# Arduino_Uno_Rev3.net
KiCad netlist of a schematic drawn in EAGLE
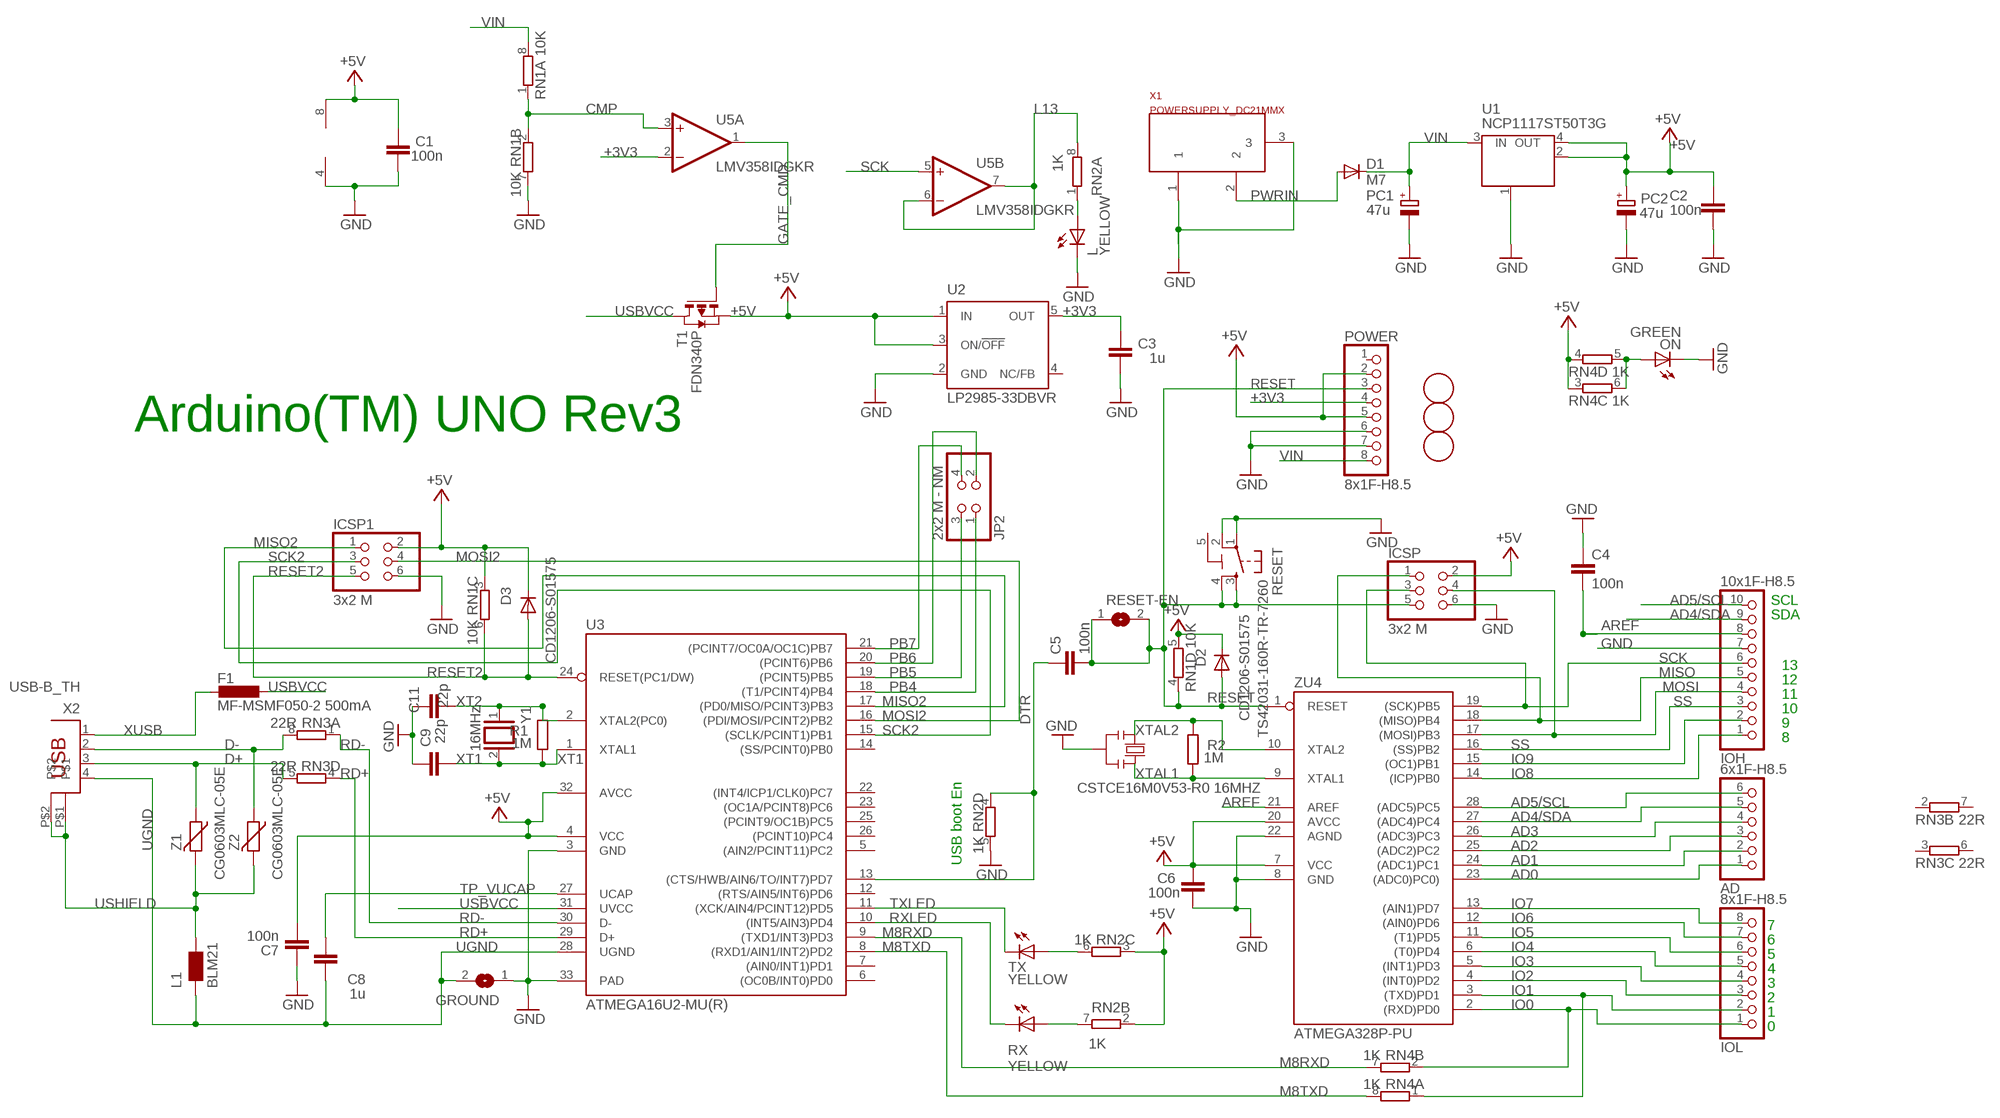
[diagram p0: schematic, sheet 1]

(export (version "E")
  (design (tool "Eeschema 10.0.6"))
  (components
    (comp (ref "AD")
      (value "6x1F-H8.5")
      (footprint "eagle-import:1X06")
      (libsource (lib "eagle-import") (part "PINHD-1X6"))
    )
    (comp (ref "C1")
      (value "100n")
      (footprint "eagle-import:C0603-ROUND")
      (libsource (lib "eagle-import") (part "C-EU0603-RND"))
    )
    (comp (ref "C2")
      (value "100n")
      (footprint "eagle-import:C0603-ROUND")
      (libsource (lib "eagle-import") (part "C-EU0603-RND"))
    )
    (comp (ref "C3")
      (value "1u")
      (footprint "eagle-import:C0603-ROUND")
      (libsource (lib "eagle-import") (part "C-EU0603-RND"))
    )
    (comp (ref "C4")
      (value "100n")
      (footprint "eagle-import:C0603-ROUND")
      (libsource (lib "eagle-import") (part "C-EU0603-RND"))
    )
    (comp (ref "C5")
      (value "100n")
      (footprint "eagle-import:C0603-ROUND")
      (libsource (lib "eagle-import") (part "C-EU0603-RND"))
    )
    (comp (ref "C6")
      (value "100n")
      (footprint "eagle-import:C0603-ROUND")
      (libsource (lib "eagle-import") (part "C-EU0603-RND"))
    )
    (comp (ref "C7")
      (value "100n")
      (footprint "eagle-import:C0603-ROUND")
      (libsource (lib "eagle-import") (part "C-EU0603-RND"))
    )
    (comp (ref "C8")
      (value "1u")
      (footprint "eagle-import:C0603-ROUND")
      (libsource (lib "eagle-import") (part "C-EU0603-RND"))
    )
    (comp (ref "C9")
      (value "22p")
      (footprint "eagle-import:C0603-ROUND")
      (libsource (lib "eagle-import") (part "C-EU0603-RND"))
    )
    (comp (ref "C11")
      (value "22p")
      (footprint "eagle-import:C0603-ROUND")
      (libsource (lib "eagle-import") (part "C-EU0603-RND"))
    )
    (comp (ref "D1")
      (value "M7")
      (footprint "eagle-import:SMB")
      (libsource (lib "eagle-import") (part "DIODE-SMB"))
    )
    (comp (ref "D2")
      (value "CD1206-S01575")
      (footprint "eagle-import:MINIMELF")
      (libsource (lib "eagle-import") (part "DIODE-MINIMELF"))
    )
    (comp (ref "D3")
      (value "CD1206-S01575")
      (footprint "eagle-import:MINIMELF")
      (libsource (lib "eagle-import") (part "DIODE-MINIMELF"))
    )
    (comp (ref "F1")
      (value "MF-MSMF050-2 500mA")
      (footprint "eagle-import:L1812")
      (libsource (lib "eagle-import") (part "L-EUL1812"))
    )
    (comp (ref "FD1")
      (value "FIDUCIALMOUNT")
      (footprint "eagle-import:FIDUCIA-MOUNT")
      (libsource (lib "eagle-import") (part "FIDUCIALMOUNT"))
    )
    (comp (ref "FD2")
      (value "FIDUCIALMOUNT")
      (footprint "eagle-import:FIDUCIA-MOUNT")
      (libsource (lib "eagle-import") (part "FIDUCIALMOUNT"))
    )
    (comp (ref "FD3")
      (value "FIDUCIALMOUNT")
      (footprint "eagle-import:FIDUCIA-MOUNT")
      (libsource (lib "eagle-import") (part "FIDUCIALMOUNT"))
    )
    (comp (ref "GROUND")
      (value "SJ")
      (footprint "eagle-import:SJ")
      (libsource (lib "eagle-import") (part "SJ"))
    )
    (comp (ref "ICSP")
      (value "3x2 M")
      (footprint "eagle-import:2X03")
      (libsource (lib "eagle-import") (part "PINHD-2X3"))
    )
    (comp (ref "ICSP1")
      (value "3x2 M")
      (footprint "eagle-import:2X03")
      (libsource (lib "eagle-import") (part "PINHD-2X3"))
    )
    (comp (ref "IOH")
      (value "10x1F-H8.5")
      (footprint "eagle-import:1X10")
      (libsource (lib "eagle-import") (part "PINHD-1X10_ARD"))
    )
    (comp (ref "IOL")
      (value "8x1F-H8.5")
      (footprint "eagle-import:1X08")
      (libsource (lib "eagle-import") (part "PINHD-1X8"))
    )
    (comp (ref "JP2")
      (value "2x2 M - NM")
      (footprint "eagle-import:2X02")
      (libsource (lib "eagle-import") (part "PINHD-2X2"))
    )
    (comp (ref "L")
      (value "YELLOW")
      (footprint "eagle-import:CHIP-LED0805")
      (libsource (lib "eagle-import") (part "LEDCHIP-LED0805"))
    )
    (comp (ref "L1")
      (value "BLM21")
      (footprint "eagle-import:0805")
      (libsource (lib "eagle-import") (part "WE-CBF_0805"))
    )
    (comp (ref "ON")
      (value "GREEN")
      (footprint "eagle-import:CHIP-LED0805")
      (libsource (lib "eagle-import") (part "LEDCHIP-LED0805"))
    )
    (comp (ref "PC1")
      (value "47u")
      (footprint "eagle-import:PANASONIC_D")
      (libsource (lib "eagle-import") (part "CPOL-EUD"))
    )
    (comp (ref "PC2")
      (value "47u")
      (footprint "eagle-import:PANASONIC_D")
      (libsource (lib "eagle-import") (part "CPOL-EUD"))
    )
    (comp (ref "POWER")
      (value "8x1F-H8.5")
      (footprint "eagle-import:1X08")
      (libsource (lib "eagle-import") (part "PINHD-1X8"))
    )
    (comp (ref "R1")
      (value "1M")
      (footprint "eagle-import:R0603-ROUND")
      (libsource (lib "eagle-import") (part "R-EU_R0603"))
    )
    (comp (ref "R2")
      (value "1M")
      (footprint "eagle-import:R0603-ROUND")
      (libsource (lib "eagle-import") (part "R-EU_R0603"))
    )
    (comp (ref "RESET")
      (value "TS42031-160R-TR-7260")
      (footprint "eagle-import:TS42")
      (libsource (lib "eagle-import") (part "TS42"))
    )
    (comp (ref "RESET-EN")
      (value "SJ")
      (footprint "eagle-import:SJ")
      (libsource (lib "eagle-import") (part "SJ"))
    )
    (comp (ref "RN1")
      (value "10K")
      (footprint "eagle-import:CAY16")
      (libsource (lib "eagle-import") (part "4R-NCAY16"))
    )
    (comp (ref "RN2")
      (value "1K")
      (footprint "eagle-import:CAY16")
      (libsource (lib "eagle-import") (part "4R-NCAY16"))
    )
    (comp (ref "RN3")
      (value "22R")
      (footprint "eagle-import:CAY16")
      (libsource (lib "eagle-import") (part "4R-NCAY16"))
    )
    (comp (ref "RN4")
      (value "1K")
      (footprint "eagle-import:CAY16")
      (libsource (lib "eagle-import") (part "4R-NCAY16"))
    )
    (comp (ref "RX")
      (value "YELLOW")
      (footprint "eagle-import:CHIP-LED0805")
      (libsource (lib "eagle-import") (part "LEDCHIP-LED0805"))
    )
    (comp (ref "T1")
      (value "FDN340P")
      (footprint "eagle-import:SOT-23")
      (libsource (lib "eagle-import") (part "PMOSSOT23"))
    )
    (comp (ref "TX")
      (value "YELLOW")
      (footprint "eagle-import:CHIP-LED0805")
      (libsource (lib "eagle-import") (part "LEDCHIP-LED0805"))
    )
    (comp (ref "U1")
      (value "NCP1117ST50T3G")
      (footprint "eagle-import:SOT223")
      (libsource (lib "eagle-import") (part "MC33269ST-3.3T3"))
    )
    (comp (ref "U2")
      (value "LP2985-33DBVR")
      (footprint "eagle-import:SOT23-DBV")
      (libsource (lib "eagle-import") (part "LP2985-XXDBVR33"))
    )
    (comp (ref "U3")
      (value "ATMEGA16U2-MU(R)")
      (footprint "eagle-import:MLF32")
      (libsource (lib "eagle-import") (part "ATMEGA16U2-MU"))
    )
    (comp (ref "U5")
      (value "LMV358IDGKR")
      (footprint "eagle-import:MSOP08")
      (libsource (lib "eagle-import") (part "LMV358?MMX"))
    )
    (comp (ref "X1")
      (value "POWERSUPPLY_DC21MMX")
      (footprint "eagle-import:POWERSUPPLY_DC-21MM")
      (libsource (lib "eagle-import") (part "POWERSUPPLY_DC21MMX"))
    )
    (comp (ref "X2")
      (value "USB-B_TH")
      (footprint "eagle-import:PN61729")
      (libsource (lib "eagle-import") (part "PN61729"))
    )
    (comp (ref "Y1")
      (value "16MHz")
      (footprint "eagle-import:QS")
      (libsource (lib "eagle-import") (part "XTAL/S"))
    )
    (comp (ref "Y2")
      (value "CSTCE16M0V53-R0 16MHZ")
      (footprint "eagle-import:RESONATOR")
      (libsource (lib "eagle-import") (part "RESONATORMU"))
    )
    (comp (ref "Z1")
      (value "CG0603MLC-05E")
      (footprint "eagle-import:CT_CN0603")
      (libsource (lib "eagle-import") (part "VARISTORCN0603"))
    )
    (comp (ref "Z2")
      (value "CG0603MLC-05E")
      (footprint "eagle-import:CT_CN0603")
      (libsource (lib "eagle-import") (part "VARISTORCN0603"))
    )
    (comp (ref "ZU4")
      (value "ATMEGA328P-PU")
      (footprint "eagle-import:DIL28-3")
      (libsource (lib "eagle-import") (part "ATMEGA328P-PU"))
    )
  )
  (nets
    (net (code "1") (name "+5V") (class "Default")
      (node (ref "C1") (pin "2") (pinfunction "2_2") (pintype "passive"))
      (node (ref "C2") (pin "2") (pinfunction "2_2") (pintype "passive"))
      (node (ref "C6") (pin "2") (pinfunction "2_2") (pintype "passive"))
      (node (ref "C7") (pin "1") (pinfunction "1_1") (pintype "passive"))
      (node (ref "D2") (pin "C") (pinfunction "C_C") (pintype "passive"))
      (node (ref "D3") (pin "C") (pinfunction "C_C") (pintype "passive"))
      (node (ref "ICSP") (pin "2") (pinfunction "2_2") (pintype "passive"))
      (node (ref "ICSP1") (pin "2") (pinfunction "2_2") (pintype "passive"))
      (node (ref "PC2") (pin "+") (pinfunction "+_+") (pintype "passive"))
      (node (ref "POWER") (pin "2") (pinfunction "2_2") (pintype "passive"))
      (node (ref "POWER") (pin "5") (pinfunction "5_5") (pintype "passive"))
      (node (ref "RN1") (pin "3") (pinfunction "1_3") (pintype "passive"))
      (node (ref "RN1") (pin "5") (pinfunction "2_5") (pintype "passive"))
      (node (ref "RN2") (pin "2") (pinfunction "1_2") (pintype "passive"))
      (node (ref "RN2") (pin "3") (pinfunction "1_3") (pintype "passive"))
      (node (ref "RN4") (pin "3") (pinfunction "1_3") (pintype "passive"))
      (node (ref "RN4") (pin "4") (pinfunction "1_4") (pintype "passive"))
      (node (ref "T1") (pin "2") (pinfunction "S_2") (pintype "passive"))
      (node (ref "U1") (pin "2") (pinfunction "OUT_2") (pintype "passive"))
      (node (ref "U1") (pin "4") (pinfunction "OUT_4") (pintype "passive"))
      (node (ref "U2") (pin "1") (pinfunction "IN_1") (pintype "input"))
      (node (ref "U2") (pin "3") (pinfunction "ON/~{OFF}_3") (pintype "input"))
      (node (ref "U3") (pin "32") (pinfunction "AVCC_32") (pintype "power_in"))
      (node (ref "U3") (pin "4") (pinfunction "VCC_4") (pintype "power_in"))
      (node (ref "U5") (pin "8") (pinfunction "V+_8") (pintype "power_in"))
      (node (ref "ZU4") (pin "20") (pinfunction "AVCC_20") (pintype "power_in"))
      (node (ref "ZU4") (pin "7") (pinfunction "VCC_7") (pintype "power_in"))
    )
    (net (code "2") (name "/+3V3") (class "Default")
      (node (ref "C3") (pin "2") (pinfunction "2_2") (pintype "passive"))
      (node (ref "POWER") (pin "4") (pinfunction "4_4") (pintype "passive"))
      (node (ref "U2") (pin "5") (pinfunction "OUT_5") (pintype "passive"))
      (node (ref "U5") (pin "2") (pinfunction "-IN_2") (pintype "input"))
    )
    (net (code "3") (name "/5-GND") (class "Default")
      (node (ref "RESET") (pin "5") (pinfunction "5-GND_5") (pintype "power_in"))
    )
    (net (code "4") (name "/AD0") (class "Default")
      (node (ref "AD") (pin "1") (pinfunction "1_1") (pintype "passive"))
      (node (ref "ZU4") (pin "23") (pinfunction "(ADC0)PC0)_23") (pintype "bidirectional"))
    )
    (net (code "5") (name "/AD1") (class "Default")
      (node (ref "AD") (pin "2") (pinfunction "2_2") (pintype "passive"))
      (node (ref "ZU4") (pin "24") (pinfunction "(ADC1)PC1_24") (pintype "bidirectional"))
    )
    (net (code "6") (name "/AD2") (class "Default")
      (node (ref "AD") (pin "3") (pinfunction "3_3") (pintype "passive"))
      (node (ref "ZU4") (pin "25") (pinfunction "(ADC2)PC2_25") (pintype "bidirectional"))
    )
    (net (code "7") (name "/AD3") (class "Default")
      (node (ref "AD") (pin "4") (pinfunction "4_4") (pintype "passive"))
      (node (ref "ZU4") (pin "26") (pinfunction "(ADC3)PC3_26") (pintype "bidirectional"))
    )
    (net (code "8") (name "/AD4{slash}SDA") (class "Default")
      (node (ref "AD") (pin "5") (pinfunction "5_5") (pintype "passive"))
      (node (ref "IOH") (pin "9") (pinfunction "9_9") (pintype "passive"))
      (node (ref "ZU4") (pin "27") (pinfunction "(ADC4)PC4_27") (pintype "bidirectional"))
    )
    (net (code "9") (name "/AD5{slash}SCL") (class "Default")
      (node (ref "AD") (pin "6") (pinfunction "6_6") (pintype "passive"))
      (node (ref "IOH") (pin "10") (pinfunction "10_10") (pintype "passive"))
      (node (ref "ZU4") (pin "28") (pinfunction "(ADC5)PC5_28") (pintype "bidirectional"))
    )
    (net (code "10") (name "/AREF") (class "Default")
      (node (ref "C4") (pin "2") (pinfunction "2_2") (pintype "passive"))
      (node (ref "IOH") (pin "8") (pinfunction "8_8") (pintype "passive"))
      (node (ref "ZU4") (pin "21") (pinfunction "AREF_21") (pintype "passive"))
    )
    (net (code "11") (name "/CMP") (class "Default")
      (node (ref "RN1") (pin "1") (pinfunction "1_1") (pintype "passive"))
      (node (ref "RN1") (pin "2") (pinfunction "1_2") (pintype "passive"))
      (node (ref "U5") (pin "3") (pinfunction "+IN_3") (pintype "input"))
    )
    (net (code "12") (name "/D+") (class "Default")
      (node (ref "RN3") (pin "5") (pinfunction "2_5") (pintype "passive"))
      (node (ref "X2") (pin "3") (pinfunction "3_3") (pintype "bidirectional"))
      (node (ref "Z1") (pin "1") (pinfunction "1_1") (pintype "passive"))
    )
    (net (code "13") (name "/D-") (class "Default")
      (node (ref "RN3") (pin "8") (pinfunction "2_8") (pintype "passive"))
      (node (ref "X2") (pin "2") (pinfunction "2_2") (pintype "bidirectional"))
      (node (ref "Z2") (pin "1") (pinfunction "1_1") (pintype "passive"))
    )
    (net (code "14") (name "/DTR") (class "Default")
      (node (ref "C5") (pin "1") (pinfunction "1_1") (pintype "passive"))
      (node (ref "RN2") (pin "4") (pinfunction "1_4") (pintype "passive"))
      (node (ref "U3") (pin "13") (pinfunction "(CTS/HWB/AIN6/TO/INT7)PD7_13") (pintype "bidirectional"))
    )
    (net (code "15") (name "/GATE_CMD") (class "Default")
      (node (ref "T1") (pin "3") (pinfunction "G_3") (pintype "passive"))
      (node (ref "U5") (pin "1") (pinfunction "OUT_1") (pintype "output"))
    )
    (net (code "16") (name "/IO0") (class "Default")
      (node (ref "IOL") (pin "1") (pinfunction "1_1") (pintype "passive"))
      (node (ref "RN4") (pin "2") (pinfunction "1_2") (pintype "passive"))
      (node (ref "ZU4") (pin "2") (pinfunction "(RXD)PD0_2") (pintype "bidirectional"))
    )
    (net (code "17") (name "/IO1") (class "Default")
      (node (ref "IOL") (pin "2") (pinfunction "2_2") (pintype "passive"))
      (node (ref "RN4") (pin "1") (pinfunction "1_1") (pintype "passive"))
      (node (ref "ZU4") (pin "3") (pinfunction "(TXD)PD1_3") (pintype "bidirectional"))
    )
    (net (code "18") (name "/IO2") (class "Default")
      (node (ref "IOL") (pin "3") (pinfunction "3_3") (pintype "passive"))
      (node (ref "ZU4") (pin "4") (pinfunction "(INT0)PD2_4") (pintype "bidirectional"))
    )
    (net (code "19") (name "/IO3") (class "Default")
      (node (ref "IOL") (pin "4") (pinfunction "4_4") (pintype "passive"))
      (node (ref "ZU4") (pin "5") (pinfunction "(INT1)PD3_5") (pintype "bidirectional"))
    )
    (net (code "20") (name "/IO4") (class "Default")
      (node (ref "IOL") (pin "5") (pinfunction "5_5") (pintype "passive"))
      (node (ref "ZU4") (pin "6") (pinfunction "(T0)PD4_6") (pintype "bidirectional"))
    )
    (net (code "21") (name "/IO5") (class "Default")
      (node (ref "IOL") (pin "6") (pinfunction "6_6") (pintype "passive"))
      (node (ref "ZU4") (pin "11") (pinfunction "(T1)PD5_11") (pintype "bidirectional"))
    )
    (net (code "22") (name "/IO6") (class "Default")
      (node (ref "IOL") (pin "7") (pinfunction "7_7") (pintype "passive"))
      (node (ref "ZU4") (pin "12") (pinfunction "(AIN0)PD6_12") (pintype "bidirectional"))
    )
    (net (code "23") (name "/IO7") (class "Default")
      (node (ref "IOL") (pin "8") (pinfunction "8_8") (pintype "passive"))
      (node (ref "ZU4") (pin "13") (pinfunction "(AIN1)PD7_13") (pintype "bidirectional"))
    )
    (net (code "24") (name "/IO8") (class "Default")
      (node (ref "IOH") (pin "1") (pinfunction "1_1") (pintype "passive"))
      (node (ref "ZU4") (pin "14") (pinfunction "(ICP)PB0_14") (pintype "bidirectional"))
    )
    (net (code "25") (name "/IO9") (class "Default")
      (node (ref "IOH") (pin "2") (pinfunction "2_2") (pintype "passive"))
      (node (ref "ZU4") (pin "15") (pinfunction "(OC1)PB1_15") (pintype "bidirectional"))
    )
    (net (code "26") (name "/L13") (class "Default")
      (node (ref "RN2") (pin "8") (pinfunction "2_8") (pintype "passive"))
      (node (ref "U5") (pin "6") (pinfunction "-IN_6") (pintype "input"))
      (node (ref "U5") (pin "7") (pinfunction "OUT_7") (pintype "output"))
    )
    (net (code "27") (name "/M8RXD") (class "Default")
      (node (ref "RN4") (pin "7") (pinfunction "2_7") (pintype "passive"))
      (node (ref "U3") (pin "9") (pinfunction "(TXD1/INT3)PD3_9") (pintype "bidirectional"))
    )
    (net (code "28") (name "/M8TXD") (class "Default")
      (node (ref "RN4") (pin "8") (pinfunction "2_8") (pintype "passive"))
      (node (ref "U3") (pin "8") (pinfunction "(RXD1/AIN1/INT2)PD2_8") (pintype "bidirectional"))
    )
    (net (code "29") (name "/MISO") (class "Default")
      (node (ref "ICSP") (pin "1") (pinfunction "1_1") (pintype "passive"))
      (node (ref "IOH") (pin "5") (pinfunction "5_5") (pintype "passive"))
      (node (ref "ZU4") (pin "18") (pinfunction "(MISO)PB4_18") (pintype "bidirectional"))
    )
    (net (code "30") (name "/MISO2") (class "Default")
      (node (ref "ICSP1") (pin "1") (pinfunction "1_1") (pintype "passive"))
      (node (ref "U3") (pin "17") (pinfunction "(PD0/MISO/PCINT3)PB3_17") (pintype "bidirectional"))
    )
    (net (code "31") (name "/MOSI") (class "Default")
      (node (ref "ICSP") (pin "4") (pinfunction "4_4") (pintype "passive"))
      (node (ref "IOH") (pin "4") (pinfunction "4_4") (pintype "passive"))
      (node (ref "ZU4") (pin "17") (pinfunction "(MOSI)PB3_17") (pintype "bidirectional"))
    )
    (net (code "32") (name "/MOSI2") (class "Default")
      (node (ref "ICSP1") (pin "4") (pinfunction "4_4") (pintype "passive"))
      (node (ref "U3") (pin "16") (pinfunction "(PDI/MOSI/PCINT2)PB2_16") (pintype "bidirectional"))
    )
    (net (code "33") (name "/PB4") (class "Default")
      (node (ref "JP2") (pin "1") (pinfunction "1_1") (pintype "passive"))
      (node (ref "U3") (pin "18") (pinfunction "(T1/PCINT4)PB4_18") (pintype "bidirectional"))
    )
    (net (code "34") (name "/PB5") (class "Default")
      (node (ref "JP2") (pin "3") (pinfunction "3_3") (pintype "passive"))
      (node (ref "U3") (pin "19") (pinfunction "(PCINT5)PB5_19") (pintype "bidirectional"))
    )
    (net (code "35") (name "/PB6") (class "Default")
      (node (ref "JP2") (pin "2") (pinfunction "2_2") (pintype "passive"))
      (node (ref "U3") (pin "20") (pinfunction "(PCINT6)PB6_20") (pintype "bidirectional"))
    )
    (net (code "36") (name "/PB7") (class "Default")
      (node (ref "JP2") (pin "4") (pinfunction "4_4") (pintype "passive"))
      (node (ref "U3") (pin "21") (pinfunction "(PCINT7/OC0A/OC1C)PB7_21") (pintype "bidirectional"))
    )
    (net (code "37") (name "/PWRIN") (class "Default")
      (node (ref "D1") (pin "A") (pinfunction "A_A") (pintype "passive"))
      (node (ref "X1") (pin "2") (pinfunction "2_2") (pintype "power_in"))
    )
    (net (code "38") (name "/RD+") (class "Default")
      (node (ref "RN3") (pin "4") (pinfunction "1_4") (pintype "passive"))
      (node (ref "U3") (pin "29") (pinfunction "D+_29") (pintype "bidirectional"))
    )
    (net (code "39") (name "/RD-") (class "Default")
      (node (ref "RN3") (pin "1") (pinfunction "1_1") (pintype "passive"))
      (node (ref "U3") (pin "30") (pinfunction "D-_30") (pintype "bidirectional"))
    )
    (net (code "40") (name "/RESET") (class "Default")
      (node (ref "C5") (pin "2") (pinfunction "2_2") (pintype "passive"))
      (node (ref "D2") (pin "A") (pinfunction "A_A") (pintype "passive"))
      (node (ref "ICSP") (pin "5") (pinfunction "5_5") (pintype "passive"))
      (node (ref "POWER") (pin "3") (pinfunction "3_3") (pintype "passive"))
      (node (ref "RESET") (pin "3") (pinfunction "3_3") (pintype "passive"))
      (node (ref "RESET") (pin "4") (pinfunction "4_4") (pintype "passive"))
      (node (ref "RESET-EN") (pin "1") (pinfunction "1_1") (pintype "passive"))
      (node (ref "RESET-EN") (pin "2") (pinfunction "2_2") (pintype "passive"))
      (node (ref "RN1") (pin "4") (pinfunction "1_4") (pintype "passive"))
      (node (ref "ZU4") (pin "1") (pinfunction "RESET_1") (pintype "input"))
    )
    (net (code "41") (name "/RESET2") (class "Default")
      (node (ref "D3") (pin "A") (pinfunction "A_A") (pintype "passive"))
      (node (ref "ICSP1") (pin "5") (pinfunction "5_5") (pintype "passive"))
      (node (ref "RN1") (pin "6") (pinfunction "2_6") (pintype "passive"))
      (node (ref "U3") (pin "24") (pinfunction "RESET(PC1/DW)_24") (pintype "input"))
    )
    (net (code "42") (name "/RXLED") (class "Default")
      (node (ref "RX") (pin "C") (pinfunction "C_C") (pintype "passive"))
      (node (ref "U3") (pin "10") (pinfunction "(INT5/AIN3)PD4_10") (pintype "bidirectional"))
    )
    (net (code "43") (name "/SCK") (class "Default")
      (node (ref "ICSP") (pin "3") (pinfunction "3_3") (pintype "passive"))
      (node (ref "IOH") (pin "6") (pinfunction "6_6") (pintype "passive"))
      (node (ref "U5") (pin "5") (pinfunction "+IN_5") (pintype "input"))
      (node (ref "ZU4") (pin "19") (pinfunction "(SCK)PB5_19") (pintype "bidirectional"))
    )
    (net (code "44") (name "/SCK2") (class "Default")
      (node (ref "ICSP1") (pin "3") (pinfunction "3_3") (pintype "passive"))
      (node (ref "U3") (pin "15") (pinfunction "(SCLK/PCINT1)PB1_15") (pintype "bidirectional"))
    )
    (net (code "45") (name "/SS") (class "Default")
      (node (ref "IOH") (pin "3") (pinfunction "3_3") (pintype "passive"))
      (node (ref "ZU4") (pin "16") (pinfunction "(SS)PB2_16") (pintype "bidirectional"))
    )
    (net (code "46") (name "/TP_VUCAP") (class "Default")
      (node (ref "C8") (pin "1") (pinfunction "1_1") (pintype "passive"))
      (node (ref "U3") (pin "27") (pinfunction "UCAP_27") (pintype "passive"))
    )
    (net (code "47") (name "/TXLED") (class "Default")
      (node (ref "TX") (pin "C") (pinfunction "C_C") (pintype "passive"))
      (node (ref "U3") (pin "11") (pinfunction "(XCK/AIN4/PCINT12)PD5_11") (pintype "bidirectional"))
    )
    (net (code "48") (name "/UGND") (class "Default")
      (node (ref "C8") (pin "2") (pinfunction "2_2") (pintype "passive"))
      (node (ref "GROUND") (pin "2") (pinfunction "2_2") (pintype "passive"))
      (node (ref "L1") (pin "1") (pinfunction "1_1") (pintype "passive"))
      (node (ref "U3") (pin "28") (pinfunction "UGND_28") (pintype "power_in"))
      (node (ref "X2") (pin "4") (pinfunction "4_4") (pintype "bidirectional"))
    )
    (net (code "49") (name "/USBVCC") (class "Default")
      (node (ref "F1") (pin "1") (pinfunction "1_1") (pintype "passive"))
      (node (ref "T1") (pin "1") (pinfunction "D_1") (pintype "passive"))
      (node (ref "U3") (pin "31") (pinfunction "UVCC_31") (pintype "power_in"))
    )
    (net (code "50") (name "/USHIELD") (class "Default")
      (node (ref "L1") (pin "2") (pinfunction "2_2") (pintype "passive"))
      (node (ref "X2") (pin "P$1") (pinfunction "P$1_P$1") (pintype "bidirectional"))
      (node (ref "X2") (pin "P$2") (pinfunction "P$2_P$2") (pintype "bidirectional"))
      (node (ref "Z1") (pin "2") (pinfunction "2_2") (pintype "passive"))
      (node (ref "Z2") (pin "2") (pinfunction "2_2") (pintype "passive"))
    )
    (net (code "51") (name "/VIN") (class "Default")
      (node (ref "D1") (pin "C") (pinfunction "C_C") (pintype "passive"))
      (node (ref "PC1") (pin "+") (pinfunction "+_+") (pintype "passive"))
      (node (ref "POWER") (pin "8") (pinfunction "8_8") (pintype "passive"))
      (node (ref "RN1") (pin "8") (pinfunction "2_8") (pintype "passive"))
      (node (ref "U1") (pin "3") (pinfunction "IN_3") (pintype "input"))
    )
    (net (code "52") (name "/XT1") (class "Default")
      (node (ref "C9") (pin "1") (pinfunction "1_1") (pintype "passive"))
      (node (ref "R1") (pin "1") (pinfunction "1_1") (pintype "passive"))
      (node (ref "U3") (pin "1") (pinfunction "XTAL1_1") (pintype "bidirectional"))
      (node (ref "Y1") (pin "2") (pinfunction "2_2") (pintype "passive"))
    )
    (net (code "53") (name "/XT2") (class "Default")
      (node (ref "C11") (pin "1") (pinfunction "1_1") (pintype "passive"))
      (node (ref "R1") (pin "2") (pinfunction "2_2") (pintype "passive"))
      (node (ref "U3") (pin "2") (pinfunction "XTAL2(PC0)_2") (pintype "bidirectional"))
      (node (ref "Y1") (pin "1") (pinfunction "1_1") (pintype "passive"))
    )
    (net (code "54") (name "/XTAL1") (class "Default")
      (node (ref "R2") (pin "1") (pinfunction "1_1") (pintype "passive"))
      (node (ref "Y2") (pin "3") (pinfunction "3_3") (pintype "passive"))
      (node (ref "ZU4") (pin "9") (pinfunction "XTAL1_9") (pintype "bidirectional"))
    )
    (net (code "55") (name "/XTAL2") (class "Default")
      (node (ref "R2") (pin "2") (pinfunction "2_2") (pintype "passive"))
      (node (ref "Y2") (pin "1") (pinfunction "1_1") (pintype "passive"))
      (node (ref "ZU4") (pin "10") (pinfunction "XTAL2_10") (pintype "bidirectional"))
    )
    (net (code "56") (name "/XUSB") (class "Default")
      (node (ref "F1") (pin "2") (pinfunction "2_2") (pintype "passive"))
      (node (ref "X2") (pin "1") (pinfunction "1_1") (pintype "bidirectional"))
    )
    (net (code "57") (name "GND") (class "Default")
      (node (ref "C1") (pin "1") (pinfunction "1_1") (pintype "passive"))
      (node (ref "C11") (pin "2") (pinfunction "2_2") (pintype "passive"))
      (node (ref "C2") (pin "1") (pinfunction "1_1") (pintype "passive"))
      (node (ref "C3") (pin "1") (pinfunction "1_1") (pintype "passive"))
      (node (ref "C4") (pin "1") (pinfunction "1_1") (pintype "passive"))
      (node (ref "C6") (pin "1") (pinfunction "1_1") (pintype "passive"))
      (node (ref "C7") (pin "2") (pinfunction "2_2") (pintype "passive"))
      (node (ref "C9") (pin "2") (pinfunction "2_2") (pintype "passive"))
      (node (ref "GROUND") (pin "1") (pinfunction "1_1") (pintype "passive"))
      (node (ref "ICSP") (pin "6") (pinfunction "6_6") (pintype "passive"))
      (node (ref "ICSP1") (pin "6") (pinfunction "6_6") (pintype "passive"))
      (node (ref "IOH") (pin "7") (pinfunction "7_7") (pintype "passive"))
      (node (ref "L") (pin "C") (pinfunction "C_C") (pintype "passive"))
      (node (ref "ON") (pin "C") (pinfunction "C_C") (pintype "passive"))
      (node (ref "PC1") (pin "-") (pinfunction "-_-") (pintype "passive"))
      (node (ref "PC2") (pin "-") (pinfunction "-_-") (pintype "passive"))
      (node (ref "POWER") (pin "6") (pinfunction "6_6") (pintype "passive"))
      (node (ref "POWER") (pin "7") (pinfunction "7_7") (pintype "passive"))
      (node (ref "RESET") (pin "1") (pinfunction "1_1") (pintype "passive"))
      (node (ref "RESET") (pin "2") (pinfunction "2_2") (pintype "passive"))
      (node (ref "RN1") (pin "7") (pinfunction "2_7") (pintype "passive"))
      (node (ref "RN2") (pin "5") (pinfunction "2_5") (pintype "passive"))
      (node (ref "U1") (pin "1") (pinfunction "GND/ADJ_1") (pintype "input"))
      (node (ref "U2") (pin "2") (pinfunction "GND_2") (pintype "power_in"))
      (node (ref "U3") (pin "3") (pinfunction "GND_3") (pintype "power_in"))
      (node (ref "U3") (pin "33") (pinfunction "PAD_33") (pintype "power_in"))
      (node (ref "U5") (pin "4") (pinfunction "V-_4") (pintype "power_in"))
      (node (ref "X1") (pin "1") (pinfunction "1_1") (pintype "power_in"))
      (node (ref "X1") (pin "3") (pinfunction "3_3") (pintype "power_in"))
      (node (ref "Y2") (pin "2") (pinfunction "2_2") (pintype "passive"))
      (node (ref "ZU4") (pin "22") (pinfunction "AGND_22") (pintype "power_in"))
      (node (ref "ZU4") (pin "8") (pinfunction "GND_8") (pintype "power_in"))
    )
    (net (code "58") (name "Net-(L-PadA)") (class "Default")
      (node (ref "L") (pin "A") (pinfunction "A_A") (pintype "passive"))
      (node (ref "RN2") (pin "1") (pinfunction "1_1") (pintype "passive"))
    )
    (net (code "59") (name "Net-(RN2B-2)") (class "Default")
      (node (ref "RN2") (pin "7") (pinfunction "2_7") (pintype "passive"))
      (node (ref "RX") (pin "A") (pinfunction "A_A") (pintype "passive"))
    )
    (net (code "60") (name "Net-(RN2C-2)") (class "Default")
      (node (ref "RN2") (pin "6") (pinfunction "2_6") (pintype "passive"))
      (node (ref "TX") (pin "A") (pinfunction "A_A") (pintype "passive"))
    )
    (net (code "61") (name "Net-(RN4C-2)") (class "Default")
      (node (ref "ON") (pin "A") (pinfunction "A_A") (pintype "passive"))
      (node (ref "RN4") (pin "5") (pinfunction "2_5") (pintype "passive"))
      (node (ref "RN4") (pin "6") (pinfunction "2_6") (pintype "passive"))
    )
    (net (code "62") (name "unconnected-(POWER-Pad1)") (class "Default")
      (node (ref "POWER") (pin "1") (pinfunction "1_1") (pintype "passive"))
    )
    (net (code "63") (name "unconnected-(RN3B-1-Pad2)") (class "Default")
      (node (ref "RN3") (pin "2") (pinfunction "1_2") (pintype "passive"))
    )
    (net (code "64") (name "unconnected-(RN3B-2-Pad7)") (class "Default")
      (node (ref "RN3") (pin "7") (pinfunction "2_7") (pintype "passive"))
    )
    (net (code "65") (name "unconnected-(RN3C-1-Pad3)") (class "Default")
      (node (ref "RN3") (pin "3") (pinfunction "1_3") (pintype "passive"))
    )
    (net (code "66") (name "unconnected-(RN3C-2-Pad6)") (class "Default")
      (node (ref "RN3") (pin "6") (pinfunction "2_6") (pintype "passive"))
    )
    (net (code "67") (name "unconnected-(U2-NC{slash}FB-Pad4)") (class "Default")
      (node (ref "U2") (pin "4") (pinfunction "NC/FB_4") (pintype "passive"))
    )
    (net (code "68") (name "unconnected-(U3-(AIN0{slash}INT1)PD1-Pad7)") (class "Default")
      (node (ref "U3") (pin "7") (pinfunction "(AIN0/INT1)PD1_7") (pintype "bidirectional"))
    )
    (net (code "69") (name "unconnected-(U3-(AIN2{slash}PCINT11)PC2-Pad5)") (class "Default")
      (node (ref "U3") (pin "5") (pinfunction "(AIN2/PCINT11)PC2_5") (pintype "bidirectional"))
    )
    (net (code "70") (name "unconnected-(U3-(INT4{slash}ICP1{slash}CLK0)PC7-Pad22)") (class "Default")
      (node (ref "U3") (pin "22") (pinfunction "(INT4/ICP1/CLK0)PC7_22") (pintype "bidirectional"))
    )
    (net (code "71") (name "unconnected-(U3-(OC0B{slash}INT0)PD0-Pad6)") (class "Default")
      (node (ref "U3") (pin "6") (pinfunction "(OC0B/INT0)PD0_6") (pintype "bidirectional"))
    )
    (net (code "72") (name "unconnected-(U3-(OC1A{slash}PCINT8)PC6-Pad23)") (class "Default")
      (node (ref "U3") (pin "23") (pinfunction "(OC1A/PCINT8)PC6_23") (pintype "bidirectional"))
    )
    (net (code "73") (name "unconnected-(U3-(PCINT9{slash}OC1B)PC5-Pad25)") (class "Default")
      (node (ref "U3") (pin "25") (pinfunction "(PCINT9/OC1B)PC5_25") (pintype "bidirectional"))
    )
    (net (code "74") (name "unconnected-(U3-(PCINT10)PC4-Pad26)") (class "Default")
      (node (ref "U3") (pin "26") (pinfunction "(PCINT10)PC4_26") (pintype "bidirectional"))
    )
    (net (code "75") (name "unconnected-(U3-(RTS{slash}AIN5{slash}INT6)PD6-Pad12)") (class "Default")
      (node (ref "U3") (pin "12") (pinfunction "(RTS/AIN5/INT6)PD6_12") (pintype "bidirectional"))
    )
    (net (code "76") (name "unconnected-(U3-(SS{slash}PCINT0)PB0-Pad14)") (class "Default")
      (node (ref "U3") (pin "14") (pinfunction "(SS/PCINT0)PB0_14") (pintype "bidirectional"))
    )
  )
)
